# touchscreen.net
KiCad netlist of a schematic drawn in Altium Designer
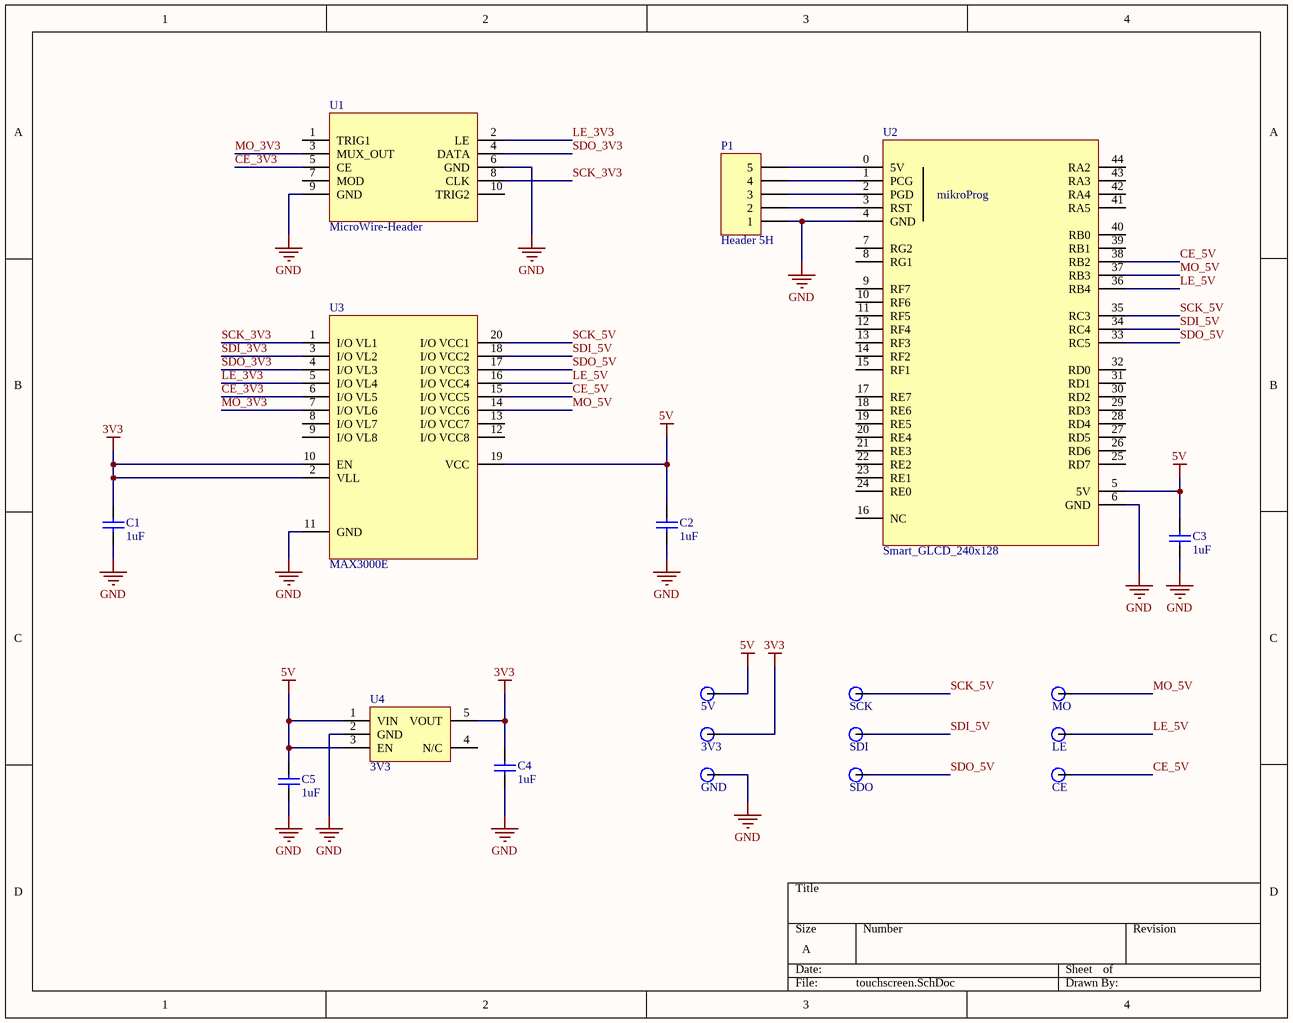
[diagram p0: touchscreen.SchDoc]

(export (version "E")
  (design (tool "Eeschema 10.0.6"))
  (components
    (comp (ref "3V3")
      (value "TP-LOOP")
      (footprint "TP-LOOP")
      (fields
        (field (name "PART NUMBER") "TP-00001")
        (field (name "MANUFACTURER") "Keystone Electronics")
        (field (name "MFG PART NUM") "5000")
      )
      (libsource (lib "savage-components") (part "TP-LOOP"))
    )
    (comp (ref "5V")
      (value "TP-LOOP")
      (footprint "TP-LOOP")
      (fields
        (field (name "PART NUMBER") "TP-00001")
        (field (name "MANUFACTURER") "Keystone Electronics")
        (field (name "MFG PART NUM") "5000")
      )
      (libsource (lib "savage-components") (part "TP-LOOP"))
    )
    (comp (ref "C1")
      (value "1uF")
      (footprint "0603-0.8MM")
      (description "Capacitor")
      (fields (field (name "PART NUMBER") "CAP-00003") (field (name "VOLTAGE") "50V"))
      (libsource (lib "savage-components") (part "CAP"))
    )
    (comp (ref "C2")
      (value "1uF")
      (footprint "0603-0.8MM")
      (description "Capacitor")
      (fields (field (name "PART NUMBER") "CAP-00003") (field (name "VOLTAGE") "50V"))
      (libsource (lib "savage-components") (part "CAP"))
    )
    (comp (ref "C3")
      (value "1uF")
      (footprint "0603-0.8MM")
      (description "Capacitor")
      (fields (field (name "PART NUMBER") "CAP-00003") (field (name "VOLTAGE") "50V"))
      (libsource (lib "savage-components") (part "CAP"))
    )
    (comp (ref "C4")
      (value "1uF")
      (footprint "0603-0.8MM")
      (description "Capacitor")
      (fields (field (name "PART NUMBER") "CAP-00003") (field (name "VOLTAGE") "50V"))
      (libsource (lib "savage-components") (part "CAP"))
    )
    (comp (ref "C5")
      (value "1uF")
      (footprint "0603-0.8MM")
      (description "Capacitor")
      (fields (field (name "PART NUMBER") "CAP-00003") (field (name "VOLTAGE") "50V"))
      (libsource (lib "savage-components") (part "CAP"))
    )
    (comp (ref "CE")
      (value "TP-LOOP")
      (footprint "TP-LOOP")
      (fields
        (field (name "PART NUMBER") "TP-00005")
        (field (name "MANUFACTURER") "Keystone Electronics")
        (field (name "MFG PART NUM") "5004")
      )
      (libsource (lib "savage-components") (part "TP-LOOP"))
    )
    (comp (ref "GND")
      (value "TP-LOOP")
      (footprint "TP-LOOP")
      (fields
        (field (name "PART NUMBER") "TP-00002")
        (field (name "MANUFACTURER") "Keystone Electronics")
        (field (name "MFG PART NUM") "5001")
      )
      (libsource (lib "savage-components") (part "TP-LOOP"))
    )
    (comp (ref "LE")
      (value "TP-LOOP")
      (footprint "TP-LOOP")
      (fields
        (field (name "PART NUMBER") "TP-00005")
        (field (name "MANUFACTURER") "Keystone Electronics")
        (field (name "MFG PART NUM") "5004")
      )
      (libsource (lib "savage-components") (part "TP-LOOP"))
    )
    (comp (ref "MO")
      (value "TP-LOOP")
      (footprint "TP-LOOP")
      (fields
        (field (name "PART NUMBER") "TP-00005")
        (field (name "MANUFACTURER") "Keystone Electronics")
        (field (name "MFG PART NUM") "5004")
      )
      (libsource (lib "savage-components") (part "TP-LOOP"))
    )
    (comp (ref "P1")
      (value "Header 5H")
      (footprint "HDR1X5H")
      (description "Header, 5-Pin, Right Angle")
      (fields
        (field (name "PART NUMBER") "CON-00002")
        (field (name "MANUFACTURER") "3M")
        (field (name "PUBLISHER") "Altium Limited")
      )
      (libsource (lib "savage-components") (part "HDR-5RA"))
    )
    (comp (ref "SCK")
      (value "TP-LOOP")
      (footprint "TP-LOOP")
      (fields
        (field (name "PART NUMBER") "TP-00005")
        (field (name "MANUFACTURER") "Keystone Electronics")
        (field (name "MFG PART NUM") "5004")
      )
      (libsource (lib "savage-components") (part "TP-LOOP"))
    )
    (comp (ref "SDI")
      (value "TP-LOOP")
      (footprint "TP-LOOP")
      (fields
        (field (name "PART NUMBER") "TP-00005")
        (field (name "MANUFACTURER") "Keystone Electronics")
        (field (name "MFG PART NUM") "5004")
      )
      (libsource (lib "savage-components") (part "TP-LOOP"))
    )
    (comp (ref "SDO")
      (value "TP-LOOP")
      (footprint "TP-LOOP")
      (fields
        (field (name "PART NUMBER") "TP-00005")
        (field (name "MANUFACTURER") "Keystone Electronics")
        (field (name "MFG PART NUM") "5004")
      )
      (libsource (lib "savage-components") (part "TP-LOOP"))
    )
    (comp (ref "U1")
      (value "MicroWire-Header")
      (footprint "HDR2x5")
      (fields
        (field (name "PART NUMBER") "CON-00001")
        (field (name "MANUFACTURER") "FCI")
        (field (name "MFG PART NUM") "52601-G10-8LF")
      )
      (libsource (lib "savage-components") (part "MicroWire-Header"))
    )
    (comp (ref "U2")
      (value "Smart_GLCD_240x128")
      (footprint "GLCD_PANEL")
      (fields
        (field (name "PART NUMBER") "MISCP-00001")
        (field (name "VOLTAGE") "5")
        (field (name "MANUFACTURER") "Mikroelektronika")
      )
      (libsource (lib "savage-components") (part "Smart_GLCD_240x128"))
    )
    (comp (ref "U3")
      (value "MAX3000E")
      (footprint "TSSOP20")
      (fields
        (field (name "PART NUMBER") "MISC-00001")
        (field (name "VOLTAGE") "1.65V - 5.5V")
        (field (name "MANUFACTURER") "Maxim Integrated")
      )
      (libsource (lib "savage-components") (part "MAX3000E"))
    )
    (comp (ref "U4")
      (value "3V3")
      (footprint "SOT-23-5")
      (fields
        (field (name "PART NUMBER") "VREG-00002")
        (field (name "MANUFACTURER") "TI")
        (field (name "MFG PART NUM") "TLV70233DBVR")
      )
      (libsource (lib "savage-components") (part "TLV70233DBVR"))
    )
  )
  (nets
    (net (code "1") (name "/CE_3V3") (class "Default")
      (node (ref "U1") (pin "5") (pinfunction "CE_5") (pintype "passive"))
      (node (ref "U3") (pin "6") (pinfunction "I/O_VL5_6") (pintype "passive"))
    )
    (net (code "2") (name "/CE_5V") (class "Default")
      (node (ref "CE") (pin "0") (pinfunction "0_0") (pintype "passive"))
      (node (ref "U2") (pin "38") (pinfunction "RB2_38") (pintype "passive"))
      (node (ref "U3") (pin "15") (pinfunction "I/O_VCC5_15") (pintype "passive"))
    )
    (net (code "3") (name "/LE_3V3") (class "Default")
      (node (ref "U1") (pin "2") (pinfunction "LE_2") (pintype "passive"))
      (node (ref "U3") (pin "5") (pinfunction "I/O_VL4_5") (pintype "passive"))
    )
    (net (code "4") (name "/LE_5V") (class "Default")
      (node (ref "LE") (pin "0") (pinfunction "0_0") (pintype "passive"))
      (node (ref "U2") (pin "36") (pinfunction "RB4_36") (pintype "passive"))
      (node (ref "U3") (pin "16") (pinfunction "I/O_VCC4_16") (pintype "passive"))
    )
    (net (code "5") (name "/MO_3V3") (class "Default")
      (node (ref "U1") (pin "3") (pinfunction "MUX_OUT_3") (pintype "passive"))
      (node (ref "U3") (pin "7") (pinfunction "I/O_VL6_7") (pintype "passive"))
    )
    (net (code "6") (name "/MO_5V") (class "Default")
      (node (ref "MO") (pin "0") (pinfunction "0_0") (pintype "passive"))
      (node (ref "U2") (pin "37") (pinfunction "RB3_37") (pintype "passive"))
      (node (ref "U3") (pin "14") (pinfunction "I/O_VCC6_14") (pintype "passive"))
    )
    (net (code "7") (name "/SCK_3V3") (class "Default")
      (node (ref "U1") (pin "8") (pinfunction "CLK_8") (pintype "passive"))
      (node (ref "U3") (pin "1") (pinfunction "I/O_VL1_1") (pintype "passive"))
    )
    (net (code "8") (name "/SCK_5V") (class "Default")
      (node (ref "SCK") (pin "0") (pinfunction "0_0") (pintype "passive"))
      (node (ref "U2") (pin "35") (pinfunction "RC3_35") (pintype "passive"))
      (node (ref "U3") (pin "20") (pinfunction "I/O_VCC1_20") (pintype "passive"))
    )
    (net (code "9") (name "/SDI_3V3") (class "Default")
      (node (ref "U3") (pin "3") (pinfunction "I/O_VL2_3") (pintype "passive"))
    )
    (net (code "10") (name "/SDI_5V") (class "Default")
      (node (ref "SDI") (pin "0") (pinfunction "0_0") (pintype "passive"))
      (node (ref "U2") (pin "34") (pinfunction "RC4_34") (pintype "passive"))
      (node (ref "U3") (pin "18") (pinfunction "I/O_VCC2_18") (pintype "passive"))
    )
    (net (code "11") (name "/SDO_3V3") (class "Default")
      (node (ref "U1") (pin "4") (pinfunction "DATA_4") (pintype "passive"))
      (node (ref "U3") (pin "4") (pinfunction "I/O_VL3_4") (pintype "passive"))
    )
    (net (code "12") (name "/SDO_5V") (class "Default")
      (node (ref "SDO") (pin "0") (pinfunction "0_0") (pintype "passive"))
      (node (ref "U2") (pin "33") (pinfunction "RC5_33") (pintype "passive"))
      (node (ref "U3") (pin "17") (pinfunction "I/O_VCC3_17") (pintype "passive"))
    )
    (net (code "13") (name "3V3") (class "Default")
      (node (ref "3V3") (pin "0") (pinfunction "0_0") (pintype "passive"))
      (node (ref "C1") (pin "2") (pinfunction "2_2") (pintype "passive"))
      (node (ref "C4") (pin "2") (pinfunction "2_2") (pintype "passive"))
      (node (ref "U3") (pin "10") (pinfunction "EN_10") (pintype "passive"))
      (node (ref "U3") (pin "2") (pinfunction "VLL_2") (pintype "passive"))
      (node (ref "U4") (pin "5") (pinfunction "VOUT_5") (pintype "passive"))
    )
    (net (code "14") (name "5V") (class "Default")
      (node (ref "5V") (pin "0") (pinfunction "0_0") (pintype "passive"))
      (node (ref "C2") (pin "2") (pinfunction "2_2") (pintype "passive"))
      (node (ref "C3") (pin "2") (pinfunction "2_2") (pintype "passive"))
      (node (ref "C5") (pin "2") (pinfunction "2_2") (pintype "passive"))
      (node (ref "U2") (pin "5") (pinfunction "5V_5") (pintype "passive"))
      (node (ref "U3") (pin "19") (pinfunction "VCC_19") (pintype "passive"))
      (node (ref "U4") (pin "1") (pinfunction "VIN_1") (pintype "passive"))
      (node (ref "U4") (pin "3") (pinfunction "EN_3") (pintype "passive"))
    )
    (net (code "15") (name "GND") (class "Default")
      (node (ref "C1") (pin "1") (pinfunction "1_1") (pintype "passive"))
      (node (ref "C2") (pin "1") (pinfunction "1_1") (pintype "passive"))
      (node (ref "C3") (pin "1") (pinfunction "1_1") (pintype "passive"))
      (node (ref "C4") (pin "1") (pinfunction "1_1") (pintype "passive"))
      (node (ref "C5") (pin "1") (pinfunction "1_1") (pintype "passive"))
      (node (ref "GND") (pin "0") (pinfunction "0_0") (pintype "passive"))
      (node (ref "P1") (pin "1") (pinfunction "1_1") (pintype "passive"))
      (node (ref "U1") (pin "6") (pinfunction "GND_6") (pintype "passive"))
      (node (ref "U1") (pin "9") (pinfunction "GND_9") (pintype "passive"))
      (node (ref "U2") (pin "4") (pinfunction "GND_4") (pintype "passive"))
      (node (ref "U2") (pin "6") (pinfunction "GND_6") (pintype "passive"))
      (node (ref "U3") (pin "11") (pinfunction "GND_11") (pintype "passive"))
      (node (ref "U4") (pin "2") (pinfunction "GND_2") (pintype "passive"))
    )
    (net (code "16") (name "Net-(P1-Pad5)") (class "Default")
      (node (ref "P1") (pin "5") (pinfunction "5_5") (pintype "passive"))
      (node (ref "U2") (pin "0") (pinfunction "5V_0") (pintype "passive"))
    )
    (net (code "17") (name "Net-(U2-PCG)") (class "Default")
      (node (ref "P1") (pin "4") (pinfunction "4_4") (pintype "passive"))
      (node (ref "U2") (pin "1") (pinfunction "PCG_1") (pintype "passive"))
    )
    (net (code "18") (name "Net-(U2-PGD)") (class "Default")
      (node (ref "P1") (pin "3") (pinfunction "3_3") (pintype "passive"))
      (node (ref "U2") (pin "2") (pinfunction "PGD_2") (pintype "passive"))
    )
    (net (code "19") (name "Net-(U2-RST)") (class "Default")
      (node (ref "P1") (pin "2") (pinfunction "2_2") (pintype "passive"))
      (node (ref "U2") (pin "3") (pinfunction "RST_3") (pintype "passive"))
    )
    (net (code "20") (name "unconnected-(U1-MOD-Pad7)") (class "Default")
      (node (ref "U1") (pin "7") (pinfunction "MOD_7") (pintype "passive"))
    )
    (net (code "21") (name "unconnected-(U1-TRIG1-Pad1)") (class "Default")
      (node (ref "U1") (pin "1") (pinfunction "TRIG1_1") (pintype "passive"))
    )
    (net (code "22") (name "unconnected-(U1-TRIG2-Pad10)") (class "Default")
      (node (ref "U1") (pin "10") (pinfunction "TRIG2_10") (pintype "passive"))
    )
    (net (code "23") (name "unconnected-(U2-NC-Pad16)") (class "Default")
      (node (ref "U2") (pin "16") (pinfunction "NC_16") (pintype "passive"))
    )
    (net (code "24") (name "unconnected-(U2-RA2-Pad44)") (class "Default")
      (node (ref "U2") (pin "44") (pinfunction "RA2_44") (pintype "passive"))
    )
    (net (code "25") (name "unconnected-(U2-RA3-Pad43)") (class "Default")
      (node (ref "U2") (pin "43") (pinfunction "RA3_43") (pintype "passive"))
    )
    (net (code "26") (name "unconnected-(U2-RA4-Pad42)") (class "Default")
      (node (ref "U2") (pin "42") (pinfunction "RA4_42") (pintype "passive"))
    )
    (net (code "27") (name "unconnected-(U2-RA5-Pad41)") (class "Default")
      (node (ref "U2") (pin "41") (pinfunction "RA5_41") (pintype "passive"))
    )
    (net (code "28") (name "unconnected-(U2-RB0-Pad40)") (class "Default")
      (node (ref "U2") (pin "40") (pinfunction "RB0_40") (pintype "passive"))
    )
    (net (code "29") (name "unconnected-(U2-RB1-Pad39)") (class "Default")
      (node (ref "U2") (pin "39") (pinfunction "RB1_39") (pintype "passive"))
    )
    (net (code "30") (name "unconnected-(U2-RD0-Pad32)") (class "Default")
      (node (ref "U2") (pin "32") (pinfunction "RD0_32") (pintype "passive"))
    )
    (net (code "31") (name "unconnected-(U2-RD1-Pad31)") (class "Default")
      (node (ref "U2") (pin "31") (pinfunction "RD1_31") (pintype "passive"))
    )
    (net (code "32") (name "unconnected-(U2-RD2-Pad30)") (class "Default")
      (node (ref "U2") (pin "30") (pinfunction "RD2_30") (pintype "passive"))
    )
    (net (code "33") (name "unconnected-(U2-RD3-Pad29)") (class "Default")
      (node (ref "U2") (pin "29") (pinfunction "RD3_29") (pintype "passive"))
    )
    (net (code "34") (name "unconnected-(U2-RD4-Pad28)") (class "Default")
      (node (ref "U2") (pin "28") (pinfunction "RD4_28") (pintype "passive"))
    )
    (net (code "35") (name "unconnected-(U2-RD5-Pad27)") (class "Default")
      (node (ref "U2") (pin "27") (pinfunction "RD5_27") (pintype "passive"))
    )
    (net (code "36") (name "unconnected-(U2-RD6-Pad26)") (class "Default")
      (node (ref "U2") (pin "26") (pinfunction "RD6_26") (pintype "passive"))
    )
    (net (code "37") (name "unconnected-(U2-RD7-Pad25)") (class "Default")
      (node (ref "U2") (pin "25") (pinfunction "RD7_25") (pintype "passive"))
    )
    (net (code "38") (name "unconnected-(U2-RE0-Pad24)") (class "Default")
      (node (ref "U2") (pin "24") (pinfunction "RE0_24") (pintype "passive"))
    )
    (net (code "39") (name "unconnected-(U2-RE1-Pad23)") (class "Default")
      (node (ref "U2") (pin "23") (pinfunction "RE1_23") (pintype "passive"))
    )
    (net (code "40") (name "unconnected-(U2-RE2-Pad22)") (class "Default")
      (node (ref "U2") (pin "22") (pinfunction "RE2_22") (pintype "passive"))
    )
    (net (code "41") (name "unconnected-(U2-RE3-Pad21)") (class "Default")
      (node (ref "U2") (pin "21") (pinfunction "RE3_21") (pintype "passive"))
    )
    (net (code "42") (name "unconnected-(U2-RE4-Pad20)") (class "Default")
      (node (ref "U2") (pin "20") (pinfunction "RE4_20") (pintype "passive"))
    )
    (net (code "43") (name "unconnected-(U2-RE5-Pad19)") (class "Default")
      (node (ref "U2") (pin "19") (pinfunction "RE5_19") (pintype "passive"))
    )
    (net (code "44") (name "unconnected-(U2-RE6-Pad18)") (class "Default")
      (node (ref "U2") (pin "18") (pinfunction "RE6_18") (pintype "passive"))
    )
    (net (code "45") (name "unconnected-(U2-RE7-Pad17)") (class "Default")
      (node (ref "U2") (pin "17") (pinfunction "RE7_17") (pintype "passive"))
    )
    (net (code "46") (name "unconnected-(U2-RF1-Pad15)") (class "Default")
      (node (ref "U2") (pin "15") (pinfunction "RF1_15") (pintype "passive"))
    )
    (net (code "47") (name "unconnected-(U2-RF2-Pad14)") (class "Default")
      (node (ref "U2") (pin "14") (pinfunction "RF2_14") (pintype "passive"))
    )
    (net (code "48") (name "unconnected-(U2-RF3-Pad13)") (class "Default")
      (node (ref "U2") (pin "13") (pinfunction "RF3_13") (pintype "passive"))
    )
    (net (code "49") (name "unconnected-(U2-RF4-Pad12)") (class "Default")
      (node (ref "U2") (pin "12") (pinfunction "RF4_12") (pintype "passive"))
    )
    (net (code "50") (name "unconnected-(U2-RF5-Pad11)") (class "Default")
      (node (ref "U2") (pin "11") (pinfunction "RF5_11") (pintype "passive"))
    )
    (net (code "51") (name "unconnected-(U2-RF6-Pad10)") (class "Default")
      (node (ref "U2") (pin "10") (pinfunction "RF6_10") (pintype "passive"))
    )
    (net (code "52") (name "unconnected-(U2-RF7-Pad9)") (class "Default")
      (node (ref "U2") (pin "9") (pinfunction "RF7_9") (pintype "passive"))
    )
    (net (code "53") (name "unconnected-(U2-RG1-Pad8)") (class "Default")
      (node (ref "U2") (pin "8") (pinfunction "RG1_8") (pintype "passive"))
    )
    (net (code "54") (name "unconnected-(U2-RG2-Pad7)") (class "Default")
      (node (ref "U2") (pin "7") (pinfunction "RG2_7") (pintype "passive"))
    )
    (net (code "55") (name "unconnected-(U3-I{slash}O_VCC7-Pad13)") (class "Default")
      (node (ref "U3") (pin "13") (pinfunction "I/O_VCC7_13") (pintype "passive"))
    )
    (net (code "56") (name "unconnected-(U3-I{slash}O_VCC8-Pad12)") (class "Default")
      (node (ref "U3") (pin "12") (pinfunction "I/O_VCC8_12") (pintype "passive"))
    )
    (net (code "57") (name "unconnected-(U3-I{slash}O_VL7-Pad8)") (class "Default")
      (node (ref "U3") (pin "8") (pinfunction "I/O_VL7_8") (pintype "passive"))
    )
    (net (code "58") (name "unconnected-(U3-I{slash}O_VL8-Pad9)") (class "Default")
      (node (ref "U3") (pin "9") (pinfunction "I/O_VL8_9") (pintype "passive"))
    )
    (net (code "59") (name "unconnected-(U4-N{slash}C-Pad4)") (class "Default")
      (node (ref "U4") (pin "4") (pinfunction "N/C_4") (pintype "passive"))
    )
  )
)
